# CanConnector.net
KiCad netlist of a schematic drawn in Altium Designer
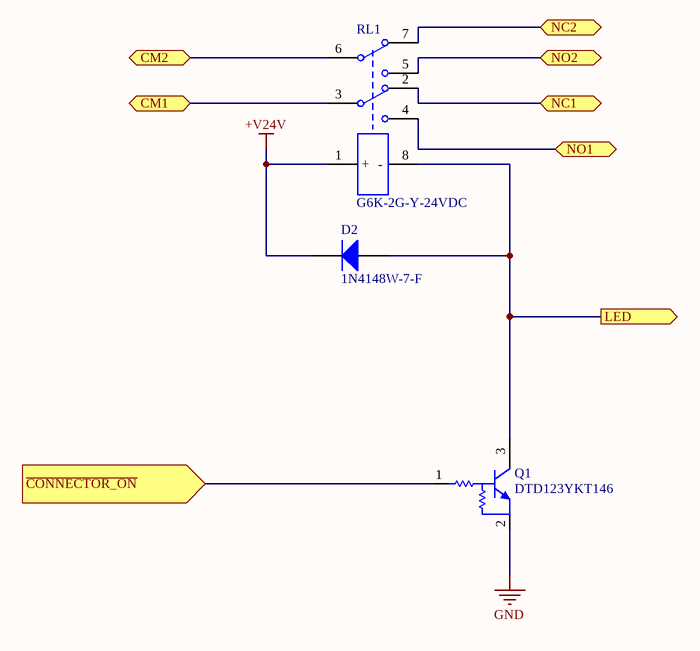
[diagram p0: CanConnector.SchDoc]

(export (version "E")
  (design (tool "Eeschema 10.0.6"))
  (components
    (comp (ref "D2")
      (value "1N4148W-7-F")
      (footprint "MC1:DIOD-SOD123-2_V")
      (description "DIODE GEN PURP 100V 300MA SOD123")
      (fields (field (name "MANUFACTURER") "Diodes") (field (name "VOLTAGE") "100V"))
      (libsource (lib "MC1") (part "1N4148W-7-F"))
    )
    (comp (ref "Q1")
      (value "DTD123YKT146")
      (footprint "MC1:SOT95P280X130-3N")
      (description "TRANS PREBIAS NPN 200MW SMT3")
      (fields (field (name "MANUFACTURER") "Rohm"))
      (libsource (lib "MC1") (part "DTD123YKT146"))
    )
    (comp (ref "RL1")
      (value "G6K-2G-Y-24VDC")
      (footprint "MC1:G6K-2F-Y")
      (description "Electromechanical Relay DPDT 1A 24VDC 5.22KOhm Surface Mount")
      (fields (field (name "MANUFACTURER") "Omron") (field (name "MANUFACTURER PART NUMBER") "G6K-2F-YDC24"))
      (libsource (lib "MC1") (part "G6K-2G-Y-24VDC"))
    )
  )
  (nets
    (net (code "1") (name "+V24V") (class "Default")
      (node (ref "D2") (pin "2") (pinfunction "K_2") (pintype "passive"))
      (node (ref "RL1") (pin "1") (pinfunction "+_1") (pintype "passive"))
    )
    (net (code "2") (name "/CM1") (class "Default")
      (node (ref "RL1") (pin "3") (pinfunction "3_3") (pintype "passive"))
    )
    (net (code "3") (name "/CM2") (class "Default")
      (node (ref "RL1") (pin "6") (pinfunction "6_6") (pintype "passive"))
    )
    (net (code "4") (name "/LED") (class "Default")
      (node (ref "D2") (pin "1") (pinfunction "A_1") (pintype "passive"))
      (node (ref "Q1") (pin "3") (pinfunction "C_3") (pintype "passive"))
      (node (ref "RL1") (pin "8") (pinfunction "-_8") (pintype "passive"))
    )
    (net (code "5") (name "/NC1") (class "Default")
      (node (ref "RL1") (pin "2") (pinfunction "2_2") (pintype "passive"))
    )
    (net (code "6") (name "/NC2") (class "Default")
      (node (ref "RL1") (pin "7") (pinfunction "7_7") (pintype "passive"))
    )
    (net (code "7") (name "/NO1") (class "Default")
      (node (ref "RL1") (pin "4") (pinfunction "4_4") (pintype "passive"))
    )
    (net (code "8") (name "/NO2") (class "Default")
      (node (ref "RL1") (pin "5") (pinfunction "5_5") (pintype "passive"))
    )
    (net (code "9") (name "/~{CONNECTOR_ON}") (class "Default")
      (node (ref "Q1") (pin "1") (pinfunction "B_1") (pintype "passive"))
    )
    (net (code "10") (name "GND") (class "Default")
      (node (ref "Q1") (pin "2") (pinfunction "E_2") (pintype "passive"))
    )
  )
)
